# 01-M2_NEO-M9N_MODULE.net
KiCad netlist of a schematic drawn in Altium Designer
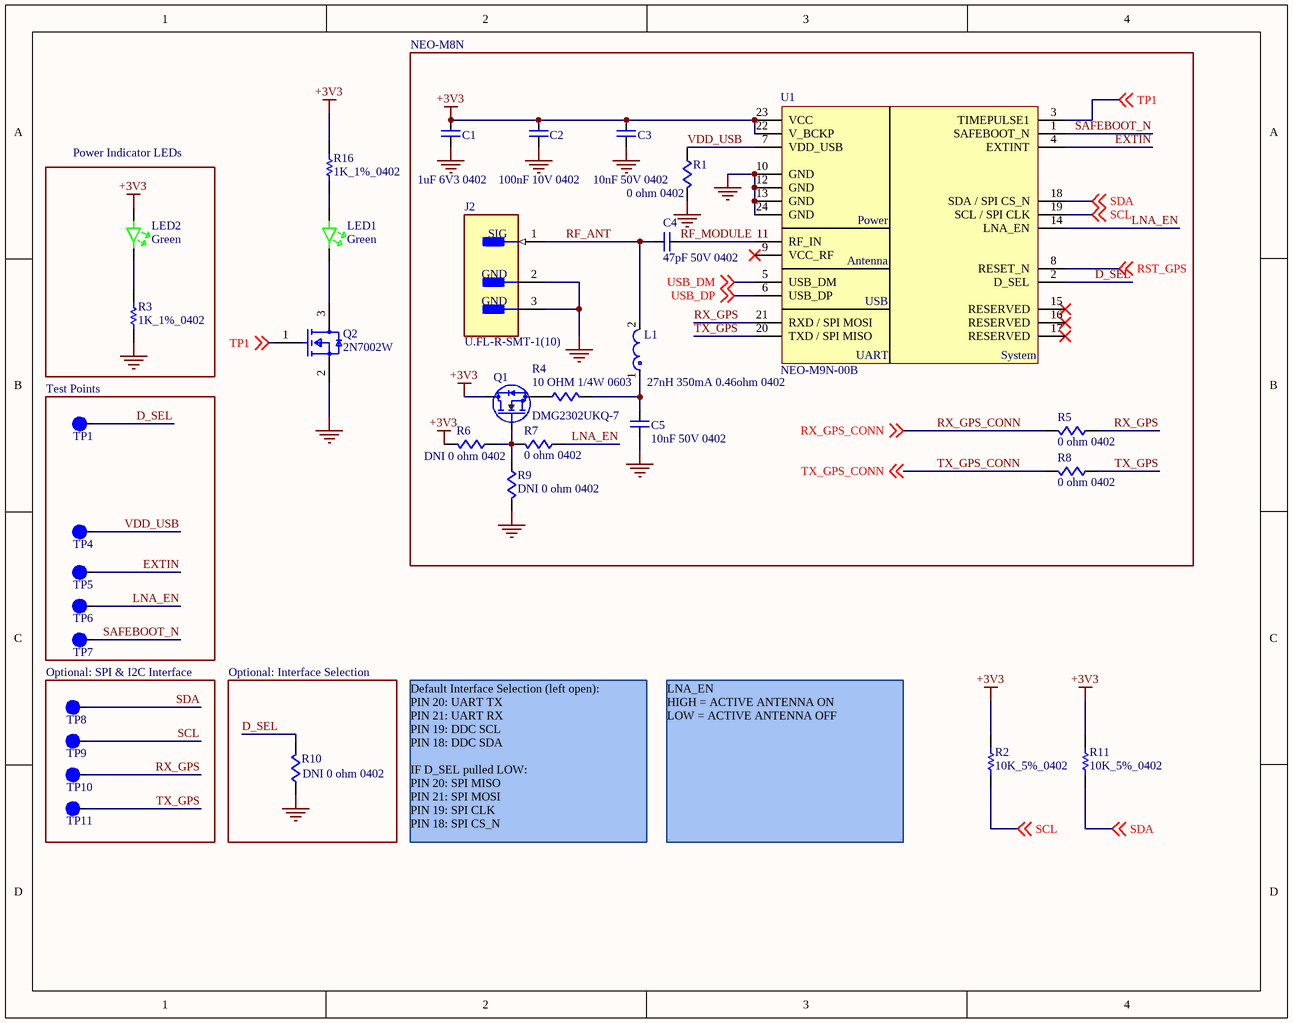
[diagram p0: 01-M2_NEO-M9N_MODULE.SchDoc]

(export (version "E")
  (design (tool "Eeschema 10.0.6"))
  (components
    (comp (ref "C1")
      (value "1uF 6V3 0402")
      (footprint "c0402")
      (description "0402 1 uF 6.3 V ±10% Tolerance X7R Multilayer Ceramic Capacitor")
      (fields
        (field (name "MANUFACTURER") "Murata")
        (field (name "MANUFACTURER PART NUMBER") "GRM155R70J105KA12J")
      )
      (libsource (lib "MyLibrary") (part "CAP CER 1UF 6.3V X7R 0402"))
    )
    (comp (ref "C2")
      (value "100nF 10V 0402")
      (footprint "c0402")
      (description "CL05 Series 0.1 uF 10 V ±10 % Tolerance X7R SMT Multilayer Ceramic Capacitor")
      (fields
        (field (name "MANUFACTURER") "Samsung")
        (field (name "MANUFACTURER PART NUMBER") "CL05B104KP5NNNC")
      )
      (libsource (lib "MyLibrary") (part "CAP CER 0.1UF 10V X7R 0402"))
    )
    (comp (ref "C3")
      (value "10nF 50V 0402")
      (footprint "c0402")
      (description "CAP CER 10000PF 50V X7R 0402")
      (fields
        (field (name "MANUFACTURER") "Murata")
        (field (name "MANUFACTURER PART NUMBER") "GCM155R71H103KA55D")
      )
      (libsource (lib "MyLibrary") (part "CAP CER 10000PF 50V X7R 0402"))
    )
    (comp (ref "C4")
      (value "47pF 50V 0402")
      (footprint "c0402")
      (description "0402 47 pF 50 V ±5 % Tolerance NP0 SMT Multilayer Ceramic Capacitor")
      (fields
        (field (name "MANUFACTURER") "Yageo")
        (field (name "MANUFACTURER PART NUMBER") "CC0402JRNPO9BN470")
      )
      (libsource (lib "MyLibrary") (part "CAP CER 47PF 50V C0G/NPO 0402"))
    )
    (comp (ref "C5")
      (value "10nF 50V 0402")
      (footprint "c0402")
      (description "CAP CER 10000PF 50V X7R 0402")
      (fields
        (field (name "MANUFACTURER") "Murata")
        (field (name "MANUFACTURER PART NUMBER") "GCM155R71H103KA55D")
      )
      (libsource (lib "MyLibrary") (part "CAP CER 10000PF 50V X7R 0402"))
    )
    (comp (ref "J2")
      (value "U.FL-R-SMT-1(10)")
      (footprint "FP-U_FL-R-SMT-1_10-MFG")
      (description "CONN U.FL RCPT STR 50 OHM SMD")
      (libsource (lib "Altium Content Vault") (part "7158abf7d987fa84906f6fb0d115710"))
    )
    (comp (ref "L1")
      (value "27nH 350mA 0.46ohm 0402")
      (footprint "FP-LQG15HH_02-IPC_C")
      (description "Multilayer type RF Inductor 27nH ±5% 0.46Ω 350mA 0402")
      (fields (field (name "TOLERANCE") "5%") (field (name "MANUFACTURER PART NUMBER") "LQG15HS27NJ02D"))
      (libsource (lib "Altium Content Vault") (part "4cc4b267dca4c8e51f7102f422741d8"))
    )
    (comp (ref "LED1")
      (value "Green")
      (footprint "led0603")
      (description "LED High-Power Uni-Color Green 574nm 2-Pin Chip LED T/R")
      (fields
        (field (name "MANUFACTURER") "Vishay Lite-On")
        (field (name "MANUFACTURER PART NUMBER") "LTST-C190KGKT")
      )
      (libsource (lib "MyLibrary") (part "LED GREEN CLEAR CHIP SMD"))
    )
    (comp (ref "LED2")
      (value "Green")
      (footprint "led0603")
      (description "LED High-Power Uni-Color Green 574nm 2-Pin Chip LED T/R")
      (fields
        (field (name "MANUFACTURER") "Vishay Lite-On")
        (field (name "MANUFACTURER PART NUMBER") "LTST-C190KGKT")
      )
      (libsource (lib "MyLibrary") (part "LED GREEN CLEAR CHIP SMD"))
    )
    (comp (ref "Q1")
      (value "DMG2302UKQ-7")
      (footprint "SOT23")
      (description "N-Channel 20 V 2.8A (Ta) 660mW (Ta) Surface Mount SOT-23-3")
      (fields
        (field (name "MANUFACTURER") "Diodes")
        (field (name "COPYRIGHT") "Copyright (C) 2022 Ultra Librarian. All rights reserved.")
      )
      (libsource (lib "MyLibrary") (part "DMG2302UKQ-7"))
    )
    (comp (ref "Q2")
      (value "2N7002W")
      (footprint "FP-419AB-01-IPC_C")
      (description "MOSFET N-CH 60V 115MA SOT-323")
      (libsource (lib "Altium Content Vault") (part "a04dfd38ebfed9f67ad7f4c51a87371"))
    )
    (comp (ref "R1")
      (value "0 ohm 0402")
      (footprint "r0402")
      (description "RES SMD 0 OHM JUMPER 1/16W 0402")
      (fields
        (field (name "MANUFACTURER") "Yageo")
        (field (name "MANUFACTURER PART NUMBER") "RC0402JR-070RL")
      )
      (libsource (lib "MyLibrary") (part "RES 0 OHM JUMPER 1/16W 0402"))
    )
    (comp (ref "R2")
      (value "10K_5%_0402")
      (footprint "RESC1005X40X25LL05T10")
      (fields (field (name "PART NUMBER") "RC0402FR-0710KL") (field (name "MANUFACTURER") "Yageo / Phycomp"))
      (libsource (lib "Altium Content Vault") (part "RES"))
    )
    (comp (ref "R3")
      (value "1K_1%_0402")
      (footprint "RESC1005X40X25NL05T05")
      (description "Chip Resistor, 1 KOhm, +/- 1%, 100 mW, -55 to 155 degC, 0402 (1005 Metric), RoHS, Tape and Reel")
      (fields (field (name "PARTNUMBER") "ERJ-2RKF1001X") (field (name "MANUFACTURER") "Basic Passives"))
      (libsource (lib "Altium Content Vault") (part "RES-2"))
    )
    (comp (ref "R4")
      (value "10 OHM 1/4W 0603")
      (footprint "r0603")
      (description "Res Surge Chip Thick Film 0603 10 Ohm 1% 1/4W ±200ppm/°C Molded Paper T/R")
      (fields
        (field (name "MANUFACTURER") "Yageo")
        (field (name "MANUFACTURER PART NUMBER") "SR0603FR-7T10RL")
      )
      (libsource (lib "MyLibrary") (part "RES SMD 10 OHM 1% 1/4W 0603"))
    )
    (comp (ref "R5")
      (value "0 ohm 0402")
      (footprint "r0402")
      (description "RES SMD 0 OHM JUMPER 1/16W 0402")
      (fields
        (field (name "MANUFACTURER") "Yageo")
        (field (name "MANUFACTURER PART NUMBER") "RC0402JR-070RL")
      )
      (libsource (lib "MyLibrary") (part "RES 0 OHM JUMPER 1/16W 0402"))
    )
    (comp (ref "R6")
      (value "DNI 0 ohm 0402")
      (footprint "r0402")
      (description "RES SMD 0 OHM JUMPER 1/16W 0402")
      (fields
        (field (name "MANUFACTURER") "Yageo")
        (field (name "MANUFACTURER PART NUMBER") "RC0402JR-070RL")
      )
      (libsource (lib "MyLibrary") (part "RES 0 OHM JUMPER 1/16W 0402"))
    )
    (comp (ref "R7")
      (value "0 ohm 0402")
      (footprint "r0402")
      (description "RES SMD 0 OHM JUMPER 1/16W 0402")
      (fields
        (field (name "MANUFACTURER") "Yageo")
        (field (name "MANUFACTURER PART NUMBER") "RC0402JR-070RL")
      )
      (libsource (lib "MyLibrary") (part "RES 0 OHM JUMPER 1/16W 0402"))
    )
    (comp (ref "R8")
      (value "0 ohm 0402")
      (footprint "r0402")
      (description "RES SMD 0 OHM JUMPER 1/16W 0402")
      (fields
        (field (name "MANUFACTURER") "Yageo")
        (field (name "MANUFACTURER PART NUMBER") "RC0402JR-070RL")
      )
      (libsource (lib "MyLibrary") (part "RES 0 OHM JUMPER 1/16W 0402"))
    )
    (comp (ref "R9")
      (value "DNI 0 ohm 0402")
      (footprint "r0402")
      (description "RES SMD 0 OHM JUMPER 1/16W 0402")
      (fields
        (field (name "MANUFACTURER") "Yageo")
        (field (name "MANUFACTURER PART NUMBER") "RC0402JR-070RL")
      )
      (libsource (lib "MyLibrary") (part "RES 0 OHM JUMPER 1/16W 0402"))
    )
    (comp (ref "R10")
      (value "DNI 0 ohm 0402")
      (footprint "r0402")
      (description "RES SMD 0 OHM JUMPER 1/16W 0402")
      (fields
        (field (name "MANUFACTURER") "Yageo")
        (field (name "MANUFACTURER PART NUMBER") "RC0402JR-070RL")
      )
      (libsource (lib "MyLibrary") (part "RES 0 OHM JUMPER 1/16W 0402"))
    )
    (comp (ref "R11")
      (value "10K_5%_0402")
      (footprint "RESC1005X40X25LL05T10")
      (fields (field (name "PART NUMBER") "RC0402FR-0710KL") (field (name "MANUFACTURER") "Yageo / Phycomp"))
      (libsource (lib "Altium Content Vault") (part "RES"))
    )
    (comp (ref "R16")
      (value "1K_1%_0402")
      (footprint "RESC1005X40X25NL05T05")
      (description "Chip Resistor, 1 KOhm, +/- 1%, 100 mW, -55 to 155 degC, 0402 (1005 Metric), RoHS, Tape and Reel")
      (fields (field (name "PARTNUMBER") "ERJ-2RKF1001X") (field (name "MANUFACTURER") "Basic Passives"))
      (libsource (lib "Altium Content Vault") (part "RES-2"))
    )
    (comp (ref "TP1")
      (value "1MM")
      (footprint "TP1MM")
      (description "Test Point 1MM diameter")
      (libsource (lib "MyLibrary") (part "TP_1MM"))
    )
    (comp (ref "TP4")
      (value "1MM")
      (footprint "TP1MM")
      (description "Test Point 1MM diameter")
      (libsource (lib "MyLibrary") (part "TP_1MM"))
    )
    (comp (ref "TP5")
      (value "1MM")
      (footprint "TP1MM")
      (description "Test Point 1MM diameter")
      (libsource (lib "MyLibrary") (part "TP_1MM"))
    )
    (comp (ref "TP6")
      (value "1MM")
      (footprint "TP1MM")
      (description "Test Point 1MM diameter")
      (libsource (lib "MyLibrary") (part "TP_1MM"))
    )
    (comp (ref "TP7")
      (value "1MM")
      (footprint "TP1MM")
      (description "Test Point 1MM diameter")
      (libsource (lib "MyLibrary") (part "TP_1MM"))
    )
    (comp (ref "TP8")
      (value "1MM")
      (footprint "TP1MM")
      (description "Test Point 1MM diameter")
      (libsource (lib "MyLibrary") (part "TP_1MM"))
    )
    (comp (ref "TP9")
      (value "1MM")
      (footprint "TP1MM")
      (description "Test Point 1MM diameter")
      (libsource (lib "MyLibrary") (part "TP_1MM"))
    )
    (comp (ref "TP10")
      (value "1MM")
      (footprint "TP1MM")
      (description "Test Point 1MM diameter")
      (libsource (lib "MyLibrary") (part "TP_1MM"))
    )
    (comp (ref "TP11")
      (value "1MM")
      (footprint "TP1MM")
      (description "Test Point 1MM diameter")
      (libsource (lib "MyLibrary") (part "TP_1MM"))
    )
    (comp (ref "U1")
      (value "NEO-M9N-00B")
      (footprint "IC_NEO-M9N")
      (description "GNSS module, Flash, TCXO, SAW, LNA, LCC, 12x16 mm Professional Grade")
      (fields (field (name "MANUFACTURER") "u-blox"))
      (libsource (lib "MyLibrary") (part "IC NEO-M9N-00B"))
    )
  )
  (nets
    (net (code "1") (name "+3V3") (class "Default")
      (node (ref "C1") (pin "2") (pinfunction "2_2") (pintype "passive"))
      (node (ref "C2") (pin "2") (pinfunction "2_2") (pintype "passive"))
      (node (ref "C3") (pin "2") (pinfunction "2_2") (pintype "passive"))
      (node (ref "LED2") (pin "1") (pinfunction "1_1") (pintype "passive"))
      (node (ref "Q1") (pin "2") (pinfunction "D_2") (pintype "passive"))
      (node (ref "R11") (pin "2") (pinfunction "2_2") (pintype "passive"))
      (node (ref "R16") (pin "2") (pinfunction "2_2") (pintype "passive"))
      (node (ref "R2") (pin "2") (pinfunction "2_2") (pintype "passive"))
      (node (ref "R6") (pin "2") (pinfunction "2_2") (pintype "passive"))
      (node (ref "U1") (pin "22") (pinfunction "V_BCKP_22") (pintype "passive"))
      (node (ref "U1") (pin "23") (pinfunction "VCC_23") (pintype "passive"))
    )
    (net (code "2") (name "/D_SEL") (class "Default")
      (node (ref "R10") (pin "2") (pinfunction "2_2") (pintype "passive"))
      (node (ref "TP1") (pin "1") (pinfunction "1_1") (pintype "passive"))
      (node (ref "U1") (pin "2") (pinfunction "D_SEL_2") (pintype "passive"))
    )
    (net (code "3") (name "/EXTIN") (class "Default")
      (node (ref "TP5") (pin "1") (pinfunction "1_1") (pintype "passive"))
      (node (ref "U1") (pin "4") (pinfunction "EXTINT_4") (pintype "passive"))
    )
    (net (code "4") (name "/LNA_EN") (class "Default")
      (node (ref "R7") (pin "1") (pinfunction "1_1") (pintype "passive"))
      (node (ref "TP6") (pin "1") (pinfunction "1_1") (pintype "passive"))
      (node (ref "U1") (pin "14") (pinfunction "LNA_EN_14") (pintype "passive"))
    )
    (net (code "5") (name "/RF_ANT") (class "Default")
      (node (ref "C4") (pin "1") (pinfunction "1_1") (pintype "passive"))
      (node (ref "J2") (pin "1") (pinfunction "SIG_1") (pintype "input"))
      (node (ref "L1") (pin "2") (pinfunction "2_2") (pintype "passive"))
    )
    (net (code "6") (name "/RF_MODULE") (class "Default")
      (node (ref "C4") (pin "2") (pinfunction "2_2") (pintype "passive"))
      (node (ref "U1") (pin "11") (pinfunction "RF_IN_11") (pintype "passive"))
    )
    (net (code "7") (name "/RX_GPS") (class "Default")
      (node (ref "R5") (pin "1") (pinfunction "1_1") (pintype "passive"))
      (node (ref "TP10") (pin "1") (pinfunction "1_1") (pintype "passive"))
      (node (ref "U1") (pin "21") (pinfunction "RXD_/_SPI_MOSI_21") (pintype "passive"))
    )
    (net (code "8") (name "/SAFEBOOT_N") (class "Default")
      (node (ref "TP7") (pin "1") (pinfunction "1_1") (pintype "passive"))
      (node (ref "U1") (pin "1") (pinfunction "SAFEBOOT_N_1") (pintype "passive"))
    )
    (net (code "9") (name "/TX_GPS") (class "Default")
      (node (ref "R8") (pin "1") (pinfunction "1_1") (pintype "passive"))
      (node (ref "TP11") (pin "1") (pinfunction "1_1") (pintype "passive"))
      (node (ref "U1") (pin "20") (pinfunction "TXD_/_SPI_MISO_20") (pintype "passive"))
    )
    (net (code "10") (name "/VDD_USB") (class "Default")
      (node (ref "R1") (pin "1") (pinfunction "1_1") (pintype "passive"))
      (node (ref "TP4") (pin "1") (pinfunction "1_1") (pintype "passive"))
      (node (ref "U1") (pin "7") (pinfunction "VDD_USB_7") (pintype "passive"))
    )
    (net (code "11") (name "GND") (class "Default")
      (node (ref "C1") (pin "1") (pinfunction "1_1") (pintype "passive"))
      (node (ref "C2") (pin "1") (pinfunction "1_1") (pintype "passive"))
      (node (ref "C3") (pin "1") (pinfunction "1_1") (pintype "passive"))
      (node (ref "C5") (pin "1") (pinfunction "1_1") (pintype "passive"))
      (node (ref "J2") (pin "2") (pinfunction "GND_2") (pintype "power_in"))
      (node (ref "J2") (pin "3") (pinfunction "GND_3") (pintype "power_in"))
      (node (ref "Q2") (pin "2") (pinfunction "Source_2") (pintype "passive"))
      (node (ref "R1") (pin "2") (pinfunction "2_2") (pintype "passive"))
      (node (ref "R10") (pin "1") (pinfunction "1_1") (pintype "passive"))
      (node (ref "R3") (pin "1") (pinfunction "1_1") (pintype "passive"))
      (node (ref "R9") (pin "2") (pinfunction "2_2") (pintype "passive"))
      (node (ref "U1") (pin "10") (pinfunction "GND_10") (pintype "passive"))
      (node (ref "U1") (pin "12") (pinfunction "GND_12") (pintype "passive"))
      (node (ref "U1") (pin "13") (pinfunction "GND_13") (pintype "passive"))
      (node (ref "U1") (pin "24") (pinfunction "GND_24") (pintype "passive"))
    )
    (net (code "12") (name "Net-(C5-Pad2)") (class "Default")
      (node (ref "C5") (pin "2") (pinfunction "2_2") (pintype "passive"))
      (node (ref "L1") (pin "1") (pinfunction "1_1") (pintype "passive"))
      (node (ref "R4") (pin "2") (pinfunction "2_2") (pintype "passive"))
    )
    (net (code "13") (name "Net-(LED1-Pad1)") (class "Default")
      (node (ref "LED1") (pin "1") (pinfunction "1_1") (pintype "passive"))
      (node (ref "R16") (pin "1") (pinfunction "1_1") (pintype "passive"))
    )
    (net (code "14") (name "Net-(LED2-Pad2)") (class "Default")
      (node (ref "LED2") (pin "2") (pinfunction "2_2") (pintype "passive"))
      (node (ref "R3") (pin "2") (pinfunction "2_2") (pintype "passive"))
    )
    (net (code "15") (name "Net-(Q1-G)") (class "Default")
      (node (ref "Q1") (pin "1") (pinfunction "G_1") (pintype "passive"))
      (node (ref "R6") (pin "1") (pinfunction "1_1") (pintype "passive"))
      (node (ref "R7") (pin "2") (pinfunction "2_2") (pintype "passive"))
      (node (ref "R9") (pin "1") (pinfunction "1_1") (pintype "passive"))
    )
    (net (code "16") (name "Net-(Q1-S)") (class "Default")
      (node (ref "Q1") (pin "3") (pinfunction "S_3") (pintype "passive"))
      (node (ref "R4") (pin "1") (pinfunction "1_1") (pintype "passive"))
    )
    (net (code "17") (name "Net-(Q2-Drain)") (class "Default")
      (node (ref "LED1") (pin "2") (pinfunction "2_2") (pintype "passive"))
      (node (ref "Q2") (pin "3") (pinfunction "Drain_3") (pintype "passive"))
    )
    (net (code "18") (name "RST_GPS") (class "Default")
      (node (ref "U1") (pin "8") (pinfunction "RESET_N_8") (pintype "passive"))
    )
    (net (code "19") (name "RX_GPS_CONN") (class "Default")
      (node (ref "R5") (pin "2") (pinfunction "2_2") (pintype "passive"))
    )
    (net (code "20") (name "SCL") (class "Default")
      (node (ref "R2") (pin "1") (pinfunction "1_1") (pintype "passive"))
      (node (ref "TP9") (pin "1") (pinfunction "1_1") (pintype "passive"))
      (node (ref "U1") (pin "19") (pinfunction "SCL_/_SPI_CLK_19") (pintype "passive"))
    )
    (net (code "21") (name "SDA") (class "Default")
      (node (ref "R11") (pin "1") (pinfunction "1_1") (pintype "passive"))
      (node (ref "TP8") (pin "1") (pinfunction "1_1") (pintype "passive"))
      (node (ref "U1") (pin "18") (pinfunction "SDA_/_SPI_CS_N_18") (pintype "passive"))
    )
    (net (code "22") (name "TP1") (class "Default")
      (node (ref "Q2") (pin "1") (pinfunction "Gate_1") (pintype "passive"))
      (node (ref "U1") (pin "3") (pinfunction "TIMEPULSE1_3") (pintype "passive"))
    )
    (net (code "23") (name "TX_GPS_CONN") (class "Default")
      (node (ref "R8") (pin "2") (pinfunction "2_2") (pintype "passive"))
    )
    (net (code "24") (name "USB_DM") (class "Default")
      (node (ref "U1") (pin "5") (pinfunction "USB_DM_5") (pintype "passive"))
    )
    (net (code "25") (name "USB_DP") (class "Default")
      (node (ref "U1") (pin "6") (pinfunction "USB_DP_6") (pintype "passive"))
    )
    (net (code "26") (name "unconnected-(U1-RESERVED-Pad15)") (class "Default")
      (node (ref "U1") (pin "15") (pinfunction "RESERVED_15") (pintype "passive+no_connect"))
    )
    (net (code "27") (name "unconnected-(U1-RESERVED-Pad16)") (class "Default")
      (node (ref "U1") (pin "16") (pinfunction "RESERVED_16") (pintype "passive+no_connect"))
    )
    (net (code "28") (name "unconnected-(U1-RESERVED-Pad17)") (class "Default")
      (node (ref "U1") (pin "17") (pinfunction "RESERVED_17") (pintype "passive+no_connect"))
    )
    (net (code "29") (name "unconnected-(U1-VCC_RF-Pad9)") (class "Default")
      (node (ref "U1") (pin "9") (pinfunction "VCC_RF_9") (pintype "passive+no_connect"))
    )
  )
)
